# untitled.net
KiCad netlist of a schematic drawn in EAGLE
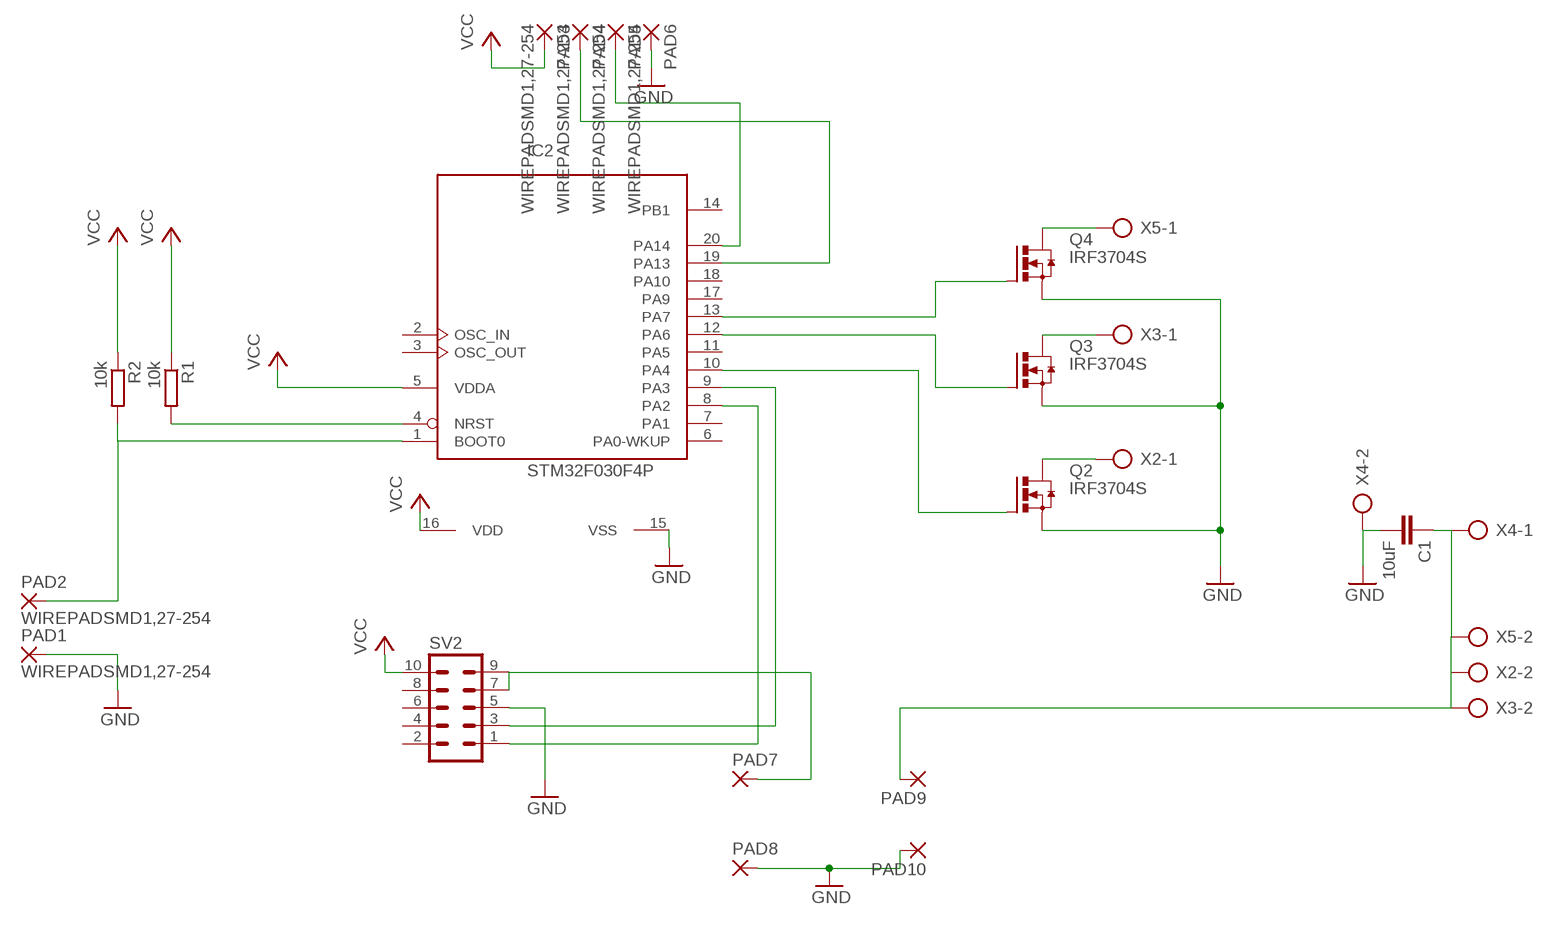
[diagram p0: schematic, sheet 1]

(export (version "E")
  (design (tool "Eeschema 10.0.6"))
  (components
    (comp (ref "C1")
      (value "10uF")
      (footprint "eagle-import:C025-050X050")
      (libsource (lib "eagle-import") (part "C-EU025-050X050"))
    )
    (comp (ref "IC2")
      (value "STM32F030F4P")
      (footprint "eagle-import:TSSOP20-I")
      (libsource (lib "eagle-import") (part "STM32F030FP4"))
    )
    (comp (ref "PAD1")
      (value "WIREPADSMD1,27-254")
      (footprint "eagle-import:SMD1,27-2,54")
      (libsource (lib "eagle-import") (part "WIREPADSMD1,27-254"))
    )
    (comp (ref "PAD2")
      (value "WIREPADSMD1,27-254")
      (footprint "eagle-import:SMD1,27-2,54")
      (libsource (lib "eagle-import") (part "WIREPADSMD1,27-254"))
    )
    (comp (ref "PAD3")
      (value "WIREPADSMD1,27-254")
      (footprint "eagle-import:SMD1,27-2,54")
      (libsource (lib "eagle-import") (part "WIREPADSMD1,27-254"))
    )
    (comp (ref "PAD4")
      (value "WIREPADSMD1,27-254")
      (footprint "eagle-import:SMD1,27-2,54")
      (libsource (lib "eagle-import") (part "WIREPADSMD1,27-254"))
    )
    (comp (ref "PAD5")
      (value "WIREPADSMD1,27-254")
      (footprint "eagle-import:SMD1,27-2,54")
      (libsource (lib "eagle-import") (part "WIREPADSMD1,27-254"))
    )
    (comp (ref "PAD6")
      (value "WIREPADSMD1,27-254")
      (footprint "eagle-import:SMD1,27-2,54")
      (libsource (lib "eagle-import") (part "WIREPADSMD1,27-254"))
    )
    (comp (ref "PAD7")
      (value "SMD5")
      (footprint "eagle-import:SMD2,54-5,08")
      (libsource (lib "eagle-import") (part "SMD5"))
    )
    (comp (ref "PAD8")
      (value "SMD5")
      (footprint "eagle-import:SMD2,54-5,08")
      (libsource (lib "eagle-import") (part "SMD5"))
    )
    (comp (ref "PAD9")
      (value "SMD5")
      (footprint "eagle-import:SMD2,54-5,08")
      (libsource (lib "eagle-import") (part "SMD5"))
    )
    (comp (ref "PAD10")
      (value "SMD5")
      (footprint "eagle-import:SMD2,54-5,08")
      (libsource (lib "eagle-import") (part "SMD5"))
    )
    (comp (ref "Q2")
      (value "IRF3704S")
      (footprint "eagle-import:D2PACK")
      (libsource (lib "eagle-import") (part "IRF3704S"))
    )
    (comp (ref "Q3")
      (value "IRF3704S")
      (footprint "eagle-import:D2PACK")
      (libsource (lib "eagle-import") (part "IRF3704S"))
    )
    (comp (ref "Q4")
      (value "IRF3704S")
      (footprint "eagle-import:D2PACK")
      (libsource (lib "eagle-import") (part "IRF3704S"))
    )
    (comp (ref "R1")
      (value "10k")
      (footprint "eagle-import:R1206")
      (libsource (lib "eagle-import") (part "R-EU_R1206"))
    )
    (comp (ref "R2")
      (value "10k")
      (footprint "eagle-import:R1206")
      (libsource (lib "eagle-import") (part "R-EU_R1206"))
    )
    (comp (ref "SV2")
      (value "MA05-2")
      (footprint "eagle-import:MA05-2")
      (libsource (lib "eagle-import") (part "MA05-2"))
    )
    (comp (ref "X2")
      (value "AK500/2")
      (footprint "eagle-import:AK500_2")
      (libsource (lib "eagle-import") (part "AK500/2"))
    )
    (comp (ref "X3")
      (value "AK500/2")
      (footprint "eagle-import:AK500_2")
      (libsource (lib "eagle-import") (part "AK500/2"))
    )
    (comp (ref "X4")
      (value "AK500/2")
      (footprint "eagle-import:AK500_2")
      (libsource (lib "eagle-import") (part "AK500/2"))
    )
    (comp (ref "X5")
      (value "AK500/2")
      (footprint "eagle-import:AK500_2")
      (libsource (lib "eagle-import") (part "AK500/2"))
    )
  )
  (nets
    (net (code "1") (name "GND") (class "Default")
      (node (ref "C1") (pin "2") (pinfunction "2_2") (pintype "passive"))
      (node (ref "IC2") (pin "15") (pinfunction "VSS_15") (pintype "power_in"))
      (node (ref "PAD1") (pin "1") (pinfunction "P_1") (pintype "passive"))
      (node (ref "PAD10") (pin "1") (pinfunction "P_1") (pintype "passive"))
      (node (ref "PAD6") (pin "1") (pinfunction "P_1") (pintype "passive"))
      (node (ref "PAD8") (pin "1") (pinfunction "P_1") (pintype "passive"))
      (node (ref "Q2") (pin "3") (pinfunction "S_3") (pintype "passive"))
      (node (ref "Q3") (pin "3") (pinfunction "S_3") (pintype "passive"))
      (node (ref "Q4") (pin "3") (pinfunction "S_3") (pintype "passive"))
      (node (ref "SV2") (pin "5") (pinfunction "5_5") (pintype "passive"))
      (node (ref "X4") (pin "2") (pinfunction "KL_2") (pintype "passive"))
    )
    (net (code "2") (name "Net-(IC2A-BOOT0)") (class "Default")
      (node (ref "IC2") (pin "1") (pinfunction "BOOT0_1") (pintype "input"))
      (node (ref "PAD2") (pin "1") (pinfunction "P_1") (pintype "passive"))
      (node (ref "R2") (pin "2") (pinfunction "2_2") (pintype "passive"))
    )
    (net (code "3") (name "Net-(IC2A-NRST)") (class "Default")
      (node (ref "IC2") (pin "4") (pinfunction "NRST_4") (pintype "bidirectional"))
      (node (ref "R1") (pin "2") (pinfunction "2_2") (pintype "passive"))
    )
    (net (code "4") (name "Net-(IC2A-PA2)") (class "Default")
      (node (ref "IC2") (pin "8") (pinfunction "PA2_8") (pintype "bidirectional"))
      (node (ref "SV2") (pin "1") (pinfunction "1_1") (pintype "passive"))
    )
    (net (code "5") (name "Net-(IC2A-PA3)") (class "Default")
      (node (ref "IC2") (pin "9") (pinfunction "PA3_9") (pintype "bidirectional"))
      (node (ref "SV2") (pin "3") (pinfunction "3_3") (pintype "passive"))
    )
    (net (code "6") (name "Net-(IC2A-PA4)") (class "Default")
      (node (ref "IC2") (pin "10") (pinfunction "PA4_10") (pintype "bidirectional"))
      (node (ref "Q2") (pin "1") (pinfunction "G_1") (pintype "passive"))
    )
    (net (code "7") (name "Net-(IC2A-PA6)") (class "Default")
      (node (ref "IC2") (pin "12") (pinfunction "PA6_12") (pintype "bidirectional"))
      (node (ref "Q3") (pin "1") (pinfunction "G_1") (pintype "passive"))
    )
    (net (code "8") (name "Net-(IC2A-PA7)") (class "Default")
      (node (ref "IC2") (pin "13") (pinfunction "PA7_13") (pintype "bidirectional"))
      (node (ref "Q4") (pin "1") (pinfunction "G_1") (pintype "passive"))
    )
    (net (code "9") (name "Net-(IC2A-PA13)") (class "Default")
      (node (ref "IC2") (pin "19") (pinfunction "PA13_19") (pintype "bidirectional"))
      (node (ref "PAD4") (pin "1") (pinfunction "P_1") (pintype "passive"))
    )
    (net (code "10") (name "Net-(IC2A-PA14)") (class "Default")
      (node (ref "IC2") (pin "20") (pinfunction "PA14_20") (pintype "bidirectional"))
      (node (ref "PAD5") (pin "1") (pinfunction "P_1") (pintype "passive"))
    )
    (net (code "11") (name "Net-(PAD7-P)") (class "Default")
      (node (ref "PAD7") (pin "1") (pinfunction "P_1") (pintype "passive"))
      (node (ref "SV2") (pin "7") (pinfunction "7_7") (pintype "passive"))
      (node (ref "SV2") (pin "9") (pinfunction "9_9") (pintype "passive"))
    )
    (net (code "12") (name "Net-(PAD9-P)") (class "Default")
      (node (ref "C1") (pin "1") (pinfunction "1_1") (pintype "passive"))
      (node (ref "PAD9") (pin "1") (pinfunction "P_1") (pintype "passive"))
      (node (ref "X2") (pin "2") (pinfunction "KL_2") (pintype "passive"))
      (node (ref "X3") (pin "2") (pinfunction "KL_2") (pintype "passive"))
      (node (ref "X4") (pin "1") (pinfunction "KL_1") (pintype "passive"))
      (node (ref "X5") (pin "2") (pinfunction "KL_2") (pintype "passive"))
    )
    (net (code "13") (name "Net-(Q2-D)") (class "Default")
      (node (ref "Q2") (pin "2") (pinfunction "D_2") (pintype "passive"))
      (node (ref "X2") (pin "1") (pinfunction "KL_1") (pintype "passive"))
    )
    (net (code "14") (name "Net-(Q3-D)") (class "Default")
      (node (ref "Q3") (pin "2") (pinfunction "D_2") (pintype "passive"))
      (node (ref "X3") (pin "1") (pinfunction "KL_1") (pintype "passive"))
    )
    (net (code "15") (name "Net-(Q4-D)") (class "Default")
      (node (ref "Q4") (pin "2") (pinfunction "D_2") (pintype "passive"))
      (node (ref "X5") (pin "1") (pinfunction "KL_1") (pintype "passive"))
    )
    (net (code "16") (name "VCC") (class "Default")
      (node (ref "IC2") (pin "16") (pinfunction "VDD_16") (pintype "power_in"))
      (node (ref "IC2") (pin "5") (pinfunction "VDDA_5") (pintype "power_in"))
      (node (ref "PAD3") (pin "1") (pinfunction "P_1") (pintype "passive"))
      (node (ref "R1") (pin "1") (pinfunction "1_1") (pintype "passive"))
      (node (ref "R2") (pin "1") (pinfunction "1_1") (pintype "passive"))
      (node (ref "SV2") (pin "10") (pinfunction "10_10") (pintype "passive"))
    )
    (net (code "17") (name "unconnected-(IC2A-OSC_IN-Pad2)") (class "Default")
      (node (ref "IC2") (pin "2") (pinfunction "OSC_IN_2") (pintype "bidirectional"))
    )
    (net (code "18") (name "unconnected-(IC2A-OSC_OUT-Pad3)") (class "Default")
      (node (ref "IC2") (pin "3") (pinfunction "OSC_OUT_3") (pintype "bidirectional"))
    )
    (net (code "19") (name "unconnected-(IC2A-PA0-WKUP-Pad6)") (class "Default")
      (node (ref "IC2") (pin "6") (pinfunction "PA0-WKUP_6") (pintype "bidirectional"))
    )
    (net (code "20") (name "unconnected-(IC2A-PA1-Pad7)") (class "Default")
      (node (ref "IC2") (pin "7") (pinfunction "PA1_7") (pintype "bidirectional"))
    )
    (net (code "21") (name "unconnected-(IC2A-PA5-Pad11)") (class "Default")
      (node (ref "IC2") (pin "11") (pinfunction "PA5_11") (pintype "bidirectional"))
    )
    (net (code "22") (name "unconnected-(IC2A-PA9-Pad17)") (class "Default")
      (node (ref "IC2") (pin "17") (pinfunction "PA9_17") (pintype "bidirectional"))
    )
    (net (code "23") (name "unconnected-(IC2A-PA10-Pad18)") (class "Default")
      (node (ref "IC2") (pin "18") (pinfunction "PA10_18") (pintype "bidirectional"))
    )
    (net (code "24") (name "unconnected-(IC2A-PB1-Pad14)") (class "Default")
      (node (ref "IC2") (pin "14") (pinfunction "PB1_14") (pintype "bidirectional"))
    )
    (net (code "25") (name "unconnected-(SV2-Pad2)") (class "Default")
      (node (ref "SV2") (pin "2") (pinfunction "2_2") (pintype "passive"))
    )
    (net (code "26") (name "unconnected-(SV2-Pad4)") (class "Default")
      (node (ref "SV2") (pin "4") (pinfunction "4_4") (pintype "passive"))
    )
    (net (code "27") (name "unconnected-(SV2-Pad6)") (class "Default")
      (node (ref "SV2") (pin "6") (pinfunction "6_6") (pintype "passive"))
    )
    (net (code "28") (name "unconnected-(SV2-Pad8)") (class "Default")
      (node (ref "SV2") (pin "8") (pinfunction "8_8") (pintype "passive"))
    )
  )
)
